# design.net
KiCad netlist of a schematic drawn in Altium Designer
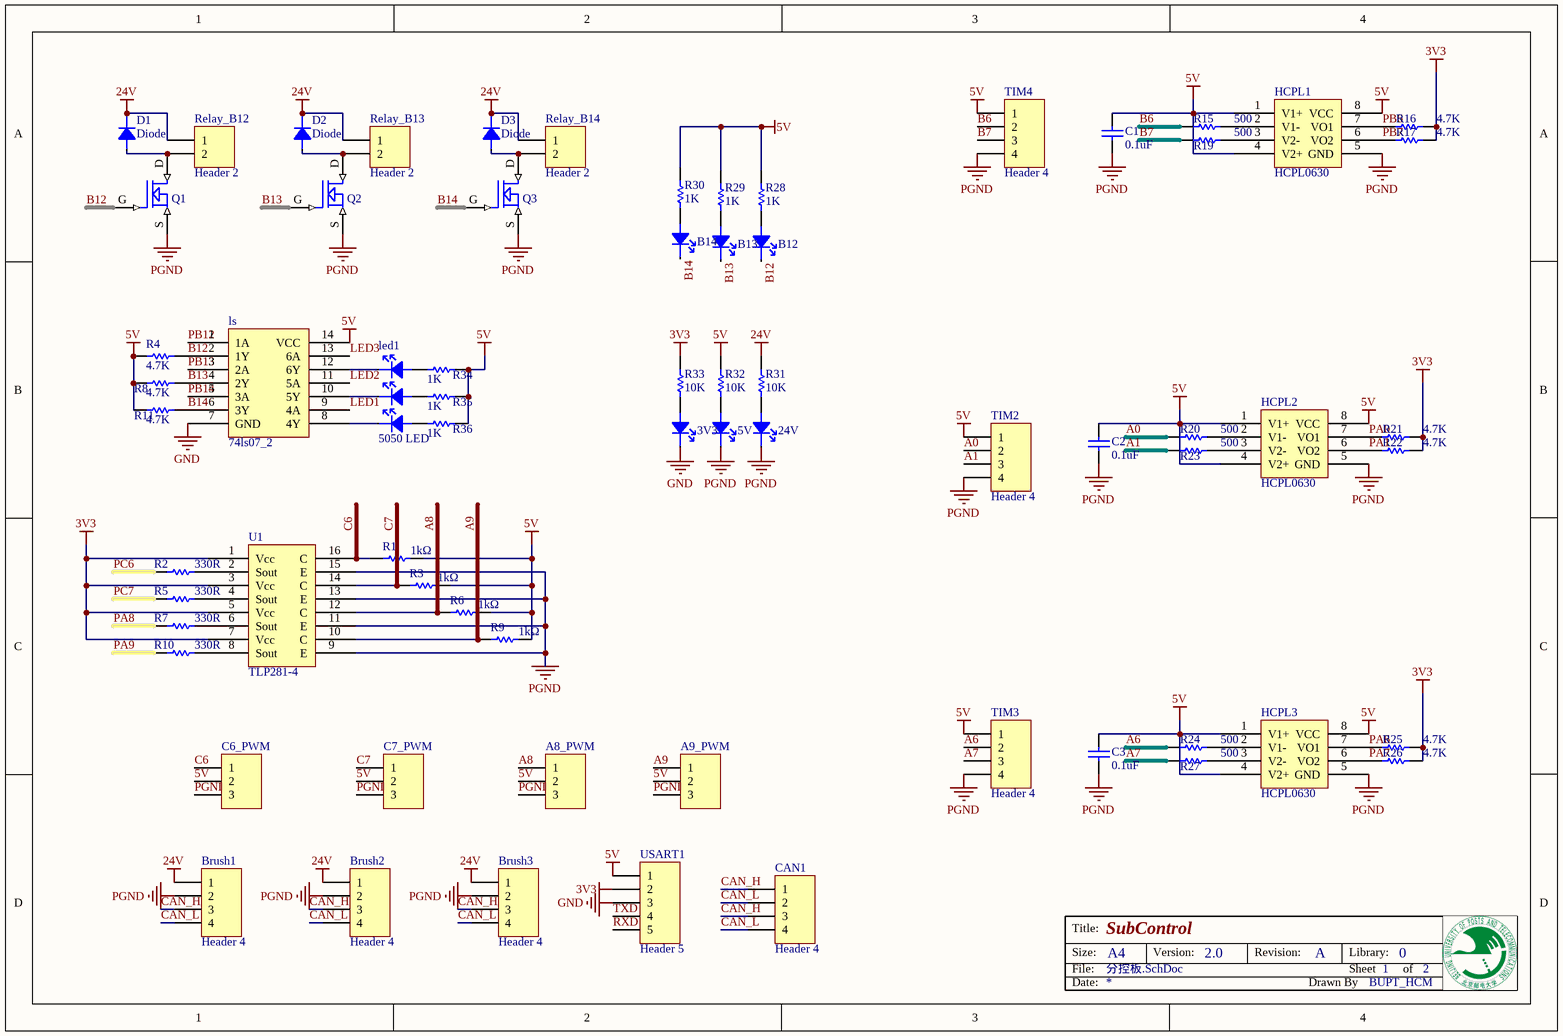
[diagram p0: 分控板.SchDoc]

(export (version "E")
  (design (tool "Eeschema 10.0.6"))
  (components
    (comp (ref "3V3")
      (value "lED")
      (footprint "0805D")
      (description "LED")
      (libsource (lib "K60-mainboard-v3.1") (part "00-D-LED"))
    )
    (comp (ref "5V")
      (value "lED")
      (footprint "0805D")
      (description "LED")
      (libsource (lib "K60-mainboard-v3.1") (part "00-D-LED"))
    )
    (comp (ref "24V")
      (value "lED")
      (footprint "0805D")
      (description "LED")
      (libsource (lib "K60-mainboard-v3.1") (part "00-D-LED"))
    )
    (comp (ref "A8_PWM")
      (value "Header 3")
      (footprint "Green 3P")
      (description "Header, 3-Pin")
      (fields (field (name "PUBLISHER") "Altium Limited"))
      (libsource (lib "Libraries_2014_0618") (part "Header 3"))
    )
    (comp (ref "A9_PWM")
      (value "Header 3")
      (footprint "Green 3P")
      (description "Header, 3-Pin")
      (fields (field (name "PUBLISHER") "Altium Limited"))
      (libsource (lib "Libraries_2014_0618") (part "Header 3"))
    )
    (comp (ref "B12")
      (value "lED")
      (footprint "0805D")
      (description "LED")
      (libsource (lib "K60-mainboard-v3.1") (part "00-D-LED"))
    )
    (comp (ref "B13")
      (value "lED")
      (footprint "0805D")
      (description "LED")
      (libsource (lib "K60-mainboard-v3.1") (part "00-D-LED"))
    )
    (comp (ref "B14")
      (value "lED")
      (footprint "0805D")
      (description "LED")
      (libsource (lib "K60-mainboard-v3.1") (part "00-D-LED"))
    )
    (comp (ref "Brush1")
      (value "Header 4")
      (footprint "Green_4P")
      (description "Header, 4-Pin")
      (fields (field (name "PUBLISHER") "Altium Limited"))
      (libsource (lib "Libraries_2014_0618") (part "Header 4"))
    )
    (comp (ref "Brush2")
      (value "Header 4")
      (footprint "Green_4P")
      (description "Header, 4-Pin")
      (fields (field (name "PUBLISHER") "Altium Limited"))
      (libsource (lib "Libraries_2014_0618") (part "Header 4"))
    )
    (comp (ref "Brush3")
      (value "Header 4")
      (footprint "Green_4P")
      (description "Header, 4-Pin")
      (fields (field (name "PUBLISHER") "Altium Limited"))
      (libsource (lib "Libraries_2014_0618") (part "Header 4"))
    )
    (comp (ref "C1")
      (value "0.1uF")
      (footprint "CAP-MLCC-0603")
      (description "Capacitor")
      (fields (field (name "Comment") "Cap") (field (name "PUBLISHER") "Altium Limited"))
      (libsource (lib "K60-mainboard-v3.1") (part "Cap"))
    )
    (comp (ref "C2")
      (value "0.1uF")
      (footprint "CAP-MLCC-0603")
      (description "Capacitor")
      (fields (field (name "Comment") "Cap") (field (name "PUBLISHER") "Altium Limited"))
      (libsource (lib "K60-mainboard-v3.1") (part "Cap"))
    )
    (comp (ref "C3")
      (value "0.1uF")
      (footprint "CAP-MLCC-0603")
      (description "Capacitor")
      (fields (field (name "Comment") "Cap") (field (name "PUBLISHER") "Altium Limited"))
      (libsource (lib "K60-mainboard-v3.1") (part "Cap"))
    )
    (comp (ref "C6_PWM")
      (value "Header 3")
      (footprint "Green 3P")
      (description "Header, 3-Pin")
      (fields (field (name "PUBLISHER") "Altium Limited"))
      (libsource (lib "Libraries_2014_0618") (part "Header 3"))
    )
    (comp (ref "C7_PWM")
      (value "Header 3")
      (footprint "Green 3P")
      (description "Header, 3-Pin")
      (fields (field (name "PUBLISHER") "Altium Limited"))
      (libsource (lib "Libraries_2014_0618") (part "Header 3"))
    )
    (comp (ref "CAN1")
      (value "Header 4")
      (footprint "Green_4P")
      (description "Header, 4-Pin")
      (fields (field (name "PUBLISHER") "Altium Limited"))
      (libsource (lib "Libraries_2014_0618") (part "Header 4"))
    )
    (comp (ref "D1") (value "Diode") (footprint "SS34") (libsource (lib "K60-mainboard-v3.1") (part "Diode")))
    (comp (ref "D2") (value "Diode") (footprint "SS34") (libsource (lib "K60-mainboard-v3.1") (part "Diode")))
    (comp (ref "D3") (value "Diode") (footprint "SS34") (libsource (lib "K60-mainboard-v3.1") (part "Diode")))
    (comp (ref "HCPL1")
      (value "HCPL0630")
      (footprint "SOIC8")
      (libsource (lib "K60-mainboard-v3.1") (part "HCPL0630"))
    )
    (comp (ref "HCPL2")
      (value "HCPL0630")
      (footprint "SOIC8")
      (libsource (lib "K60-mainboard-v3.1") (part "HCPL0630"))
    )
    (comp (ref "HCPL3")
      (value "HCPL0630")
      (footprint "SOIC8")
      (libsource (lib "K60-mainboard-v3.1") (part "HCPL0630"))
    )
    (comp (ref "led1")
      (value "5050 LED")
      (footprint "5050LED")
      (libsource (lib "K60-mainboard-v3.1") (part "5050 LED"))
    )
    (comp (ref "ls")
      (value "74ls07_2")
      (footprint "74ls07")
      (libsource (lib "K60-mainboard-v3.1") (part "74ls07_2"))
    )
    (comp (ref "Q1")
      (value "MOSFET N")
      (footprint "NMOS_SOT23")
      (libsource (lib "K60-mainboard-v3.1") (part "MOSFET N"))
    )
    (comp (ref "Q2")
      (value "MOSFET N")
      (footprint "NMOS_SOT23")
      (libsource (lib "K60-mainboard-v3.1") (part "MOSFET N"))
    )
    (comp (ref "Q3")
      (value "MOSFET N")
      (footprint "NMOS_SOT23")
      (libsource (lib "K60-mainboard-v3.1") (part "MOSFET N"))
    )
    (comp (ref "R1")
      (value "1kΩ")
      (footprint "RES-0603")
      (description "电阻")
      (fields (field (name "Comment") "RES") (field (name "PUBLISHER") "Altium Limited"))
      (libsource (lib "Libraries_2014_0215") (part "RES"))
    )
    (comp (ref "R2")
      (value "330R")
      (footprint "RES-0603")
      (description "电阻")
      (fields (field (name "Comment") "RES") (field (name "PUBLISHER") "Altium Limited"))
      (libsource (lib "Libraries_2014_0215") (part "RES"))
    )
    (comp (ref "R3")
      (value "1kΩ")
      (footprint "RES-0603")
      (description "电阻")
      (fields (field (name "Comment") "RES") (field (name "PUBLISHER") "Altium Limited"))
      (libsource (lib "Libraries_2014_0215") (part "RES"))
    )
    (comp (ref "R4")
      (value "4.7K")
      (footprint "RES-0603")
      (description "电阻")
      (fields (field (name "Comment") "RES") (field (name "PUBLISHER") "Altium Limited"))
      (libsource (lib "Libraries_2014_0215") (part "RES"))
    )
    (comp (ref "R5")
      (value "330R")
      (footprint "RES-0603")
      (description "电阻")
      (fields (field (name "Comment") "RES") (field (name "PUBLISHER") "Altium Limited"))
      (libsource (lib "Libraries_2014_0215") (part "RES"))
    )
    (comp (ref "R6")
      (value "1kΩ")
      (footprint "RES-0603")
      (description "电阻")
      (fields (field (name "Comment") "RES") (field (name "PUBLISHER") "Altium Limited"))
      (libsource (lib "Libraries_2014_0215") (part "RES"))
    )
    (comp (ref "R7")
      (value "330R")
      (footprint "RES-0603")
      (description "电阻")
      (fields (field (name "Comment") "RES") (field (name "PUBLISHER") "Altium Limited"))
      (libsource (lib "Libraries_2014_0215") (part "RES"))
    )
    (comp (ref "R8")
      (value "4.7K")
      (footprint "RES-0603")
      (description "电阻")
      (fields (field (name "Comment") "RES") (field (name "PUBLISHER") "Altium Limited"))
      (libsource (lib "Libraries_2014_0215") (part "RES"))
    )
    (comp (ref "R9")
      (value "1kΩ")
      (footprint "RES-0603")
      (description "电阻")
      (fields (field (name "Comment") "RES") (field (name "PUBLISHER") "Altium Limited"))
      (libsource (lib "Libraries_2014_0215") (part "RES"))
    )
    (comp (ref "R10")
      (value "330R")
      (footprint "RES-0603")
      (description "电阻")
      (fields (field (name "Comment") "RES") (field (name "PUBLISHER") "Altium Limited"))
      (libsource (lib "Libraries_2014_0215") (part "RES"))
    )
    (comp (ref "R11")
      (value "4.7K")
      (footprint "RES-0603")
      (description "电阻")
      (fields (field (name "Comment") "RES") (field (name "PUBLISHER") "Altium Limited"))
      (libsource (lib "Libraries_2014_0215") (part "RES"))
    )
    (comp (ref "R15")
      (value "500")
      (footprint "RES-0603")
      (description "Resistor")
      (fields (field (name "Comment") "Res1") (field (name "PUBLISHER") "Altium Limited"))
      (libsource (lib "K60-mainboard-v3.1") (part "Res1"))
    )
    (comp (ref "R16")
      (value "4.7K")
      (footprint "RES-0603")
      (description "Resistor")
      (fields (field (name "Comment") "Res1") (field (name "PUBLISHER") "Altium Limited"))
      (libsource (lib "K60-mainboard-v3.1") (part "Res1"))
    )
    (comp (ref "R17")
      (value "4.7K")
      (footprint "RES-0603")
      (description "Resistor")
      (fields (field (name "Comment") "Res1") (field (name "PUBLISHER") "Altium Limited"))
      (libsource (lib "K60-mainboard-v3.1") (part "Res1"))
    )
    (comp (ref "R19")
      (value "500")
      (footprint "RES-0603")
      (description "Resistor")
      (fields (field (name "Comment") "Res1") (field (name "PUBLISHER") "Altium Limited"))
      (libsource (lib "K60-mainboard-v3.1") (part "Res1"))
    )
    (comp (ref "R20")
      (value "500")
      (footprint "RES-0603")
      (description "Resistor")
      (fields (field (name "Comment") "Res1") (field (name "PUBLISHER") "Altium Limited"))
      (libsource (lib "K60-mainboard-v3.1") (part "Res1"))
    )
    (comp (ref "R21")
      (value "4.7K")
      (footprint "RES-0603")
      (description "Resistor")
      (fields (field (name "Comment") "Res1") (field (name "PUBLISHER") "Altium Limited"))
      (libsource (lib "K60-mainboard-v3.1") (part "Res1"))
    )
    (comp (ref "R22")
      (value "4.7K")
      (footprint "RES-0603")
      (description "Resistor")
      (fields (field (name "Comment") "Res1") (field (name "PUBLISHER") "Altium Limited"))
      (libsource (lib "K60-mainboard-v3.1") (part "Res1"))
    )
    (comp (ref "R23")
      (value "500")
      (footprint "RES-0603")
      (description "Resistor")
      (fields (field (name "Comment") "Res1") (field (name "PUBLISHER") "Altium Limited"))
      (libsource (lib "K60-mainboard-v3.1") (part "Res1"))
    )
    (comp (ref "R24")
      (value "500")
      (footprint "RES-0603")
      (description "Resistor")
      (fields (field (name "Comment") "Res1") (field (name "PUBLISHER") "Altium Limited"))
      (libsource (lib "K60-mainboard-v3.1") (part "Res1"))
    )
    (comp (ref "R25")
      (value "4.7K")
      (footprint "RES-0603")
      (description "Resistor")
      (fields (field (name "Comment") "Res1") (field (name "PUBLISHER") "Altium Limited"))
      (libsource (lib "K60-mainboard-v3.1") (part "Res1"))
    )
    (comp (ref "R26")
      (value "4.7K")
      (footprint "RES-0603")
      (description "Resistor")
      (fields (field (name "Comment") "Res1") (field (name "PUBLISHER") "Altium Limited"))
      (libsource (lib "K60-mainboard-v3.1") (part "Res1"))
    )
    (comp (ref "R27")
      (value "500")
      (footprint "RES-0603")
      (description "Resistor")
      (fields (field (name "Comment") "Res1") (field (name "PUBLISHER") "Altium Limited"))
      (libsource (lib "K60-mainboard-v3.1") (part "Res1"))
    )
    (comp (ref "R28")
      (value "1K")
      (footprint "RES-0603")
      (description "电阻")
      (fields (field (name "Comment") "RES") (field (name "PUBLISHER") "Altium Limited"))
      (libsource (lib "Libraries_2014_0215") (part "RES"))
    )
    (comp (ref "R29")
      (value "1K")
      (footprint "RES-0603")
      (description "电阻")
      (fields (field (name "Comment") "RES") (field (name "PUBLISHER") "Altium Limited"))
      (libsource (lib "Libraries_2014_0215") (part "RES"))
    )
    (comp (ref "R30")
      (value "1K")
      (footprint "RES-0603")
      (description "电阻")
      (fields (field (name "Comment") "RES") (field (name "PUBLISHER") "Altium Limited"))
      (libsource (lib "Libraries_2014_0215") (part "RES"))
    )
    (comp (ref "R31")
      (value "10K")
      (footprint "RES-0603")
      (description "电阻")
      (fields (field (name "Comment") "RES") (field (name "PUBLISHER") "Altium Limited"))
      (libsource (lib "Libraries_2014_0215") (part "RES"))
    )
    (comp (ref "R32")
      (value "10K")
      (footprint "RES-0603")
      (description "电阻")
      (fields (field (name "Comment") "RES") (field (name "PUBLISHER") "Altium Limited"))
      (libsource (lib "Libraries_2014_0215") (part "RES"))
    )
    (comp (ref "R33")
      (value "10K")
      (footprint "RES-0603")
      (description "电阻")
      (fields (field (name "Comment") "RES") (field (name "PUBLISHER") "Altium Limited"))
      (libsource (lib "Libraries_2014_0215") (part "RES"))
    )
    (comp (ref "R34")
      (value "1K")
      (footprint "RES-0603")
      (description "电阻")
      (fields (field (name "Comment") "RES") (field (name "PUBLISHER") "Altium Limited"))
      (libsource (lib "Libraries_2014_0215") (part "RES"))
    )
    (comp (ref "R35")
      (value "1K")
      (footprint "RES-0603")
      (description "电阻")
      (fields (field (name "Comment") "RES") (field (name "PUBLISHER") "Altium Limited"))
      (libsource (lib "Libraries_2014_0215") (part "RES"))
    )
    (comp (ref "R36")
      (value "1K")
      (footprint "RES-0603")
      (description "电阻")
      (fields (field (name "Comment") "RES") (field (name "PUBLISHER") "Altium Limited"))
      (libsource (lib "Libraries_2014_0215") (part "RES"))
    )
    (comp (ref "Relay_B12")
      (value "Header 2")
      (footprint "Green_2P")
      (description "Header, 2-Pin")
      (fields (field (name "PUBLISHER") "Altium Limited"))
      (libsource (lib "K60-mainboard-v3.1") (part "Header 2"))
    )
    (comp (ref "Relay_B13")
      (value "Header 2")
      (footprint "Green_2P")
      (description "Header, 2-Pin")
      (fields (field (name "PUBLISHER") "Altium Limited"))
      (libsource (lib "K60-mainboard-v3.1") (part "Header 2"))
    )
    (comp (ref "Relay_B14")
      (value "Header 2")
      (footprint "Green_2P")
      (description "Header, 2-Pin")
      (fields (field (name "PUBLISHER") "Altium Limited"))
      (libsource (lib "K60-mainboard-v3.1") (part "Header 2"))
    )
    (comp (ref "TIM2")
      (value "Header 4")
      (footprint "Green_4P")
      (description "Header, 4-Pin")
      (fields (field (name "PUBLISHER") "Altium Limited"))
      (libsource (lib "Libraries_2014_0618") (part "Header 4"))
    )
    (comp (ref "TIM3")
      (value "Header 4")
      (footprint "Green_4P")
      (description "Header, 4-Pin")
      (fields (field (name "PUBLISHER") "Altium Limited"))
      (libsource (lib "Libraries_2014_0618") (part "Header 4"))
    )
    (comp (ref "TIM4")
      (value "Header 4")
      (footprint "Green_4P")
      (description "Header, 4-Pin")
      (fields (field (name "PUBLISHER") "Altium Limited"))
      (libsource (lib "Libraries_2014_0618") (part "Header 4"))
    )
    (comp (ref "U1")
      (value "TLP281-4")
      (footprint "SOP16")
      (description "TLP521-4,TLP281-4")
      (libsource (lib "Libraries_2014_0215") (part "IC-TLP521-4"))
    )
    (comp (ref "USART1")
      (value "Header 5")
      (footprint "Green_5P")
      (description "Header, 5-Pin")
      (fields (field (name "PUBLISHER") "Altium Limited"))
      (libsource (lib "Libraries_2014_0618") (part "Header 5"))
    )
  )
  (nets
    (net (code "1") (name "/A0") (class "Default")
      (node (ref "R20") (pin "1") (pinfunction "1_1") (pintype "passive"))
      (node (ref "TIM2") (pin "2") (pinfunction "2_2") (pintype "passive"))
    )
    (net (code "2") (name "/A1") (class "Default")
      (node (ref "R23") (pin "1") (pinfunction "1_1") (pintype "passive"))
      (node (ref "TIM2") (pin "3") (pinfunction "3_3") (pintype "passive"))
    )
    (net (code "3") (name "/A6") (class "Default")
      (node (ref "R24") (pin "1") (pinfunction "1_1") (pintype "passive"))
      (node (ref "TIM3") (pin "2") (pinfunction "2_2") (pintype "passive"))
    )
    (net (code "4") (name "/A7") (class "Default")
      (node (ref "R27") (pin "1") (pinfunction "1_1") (pintype "passive"))
      (node (ref "TIM3") (pin "3") (pinfunction "3_3") (pintype "passive"))
    )
    (net (code "5") (name "/A8") (class "Default")
      (node (ref "A8_PWM") (pin "1") (pinfunction "1_1") (pintype "passive"))
      (node (ref "R6") (pin "1") (pinfunction "1_1") (pintype "passive"))
      (node (ref "U1") (pin "12") (pinfunction "C_12") (pintype "power_in"))
    )
    (net (code "6") (name "/A9") (class "Default")
      (node (ref "A9_PWM") (pin "1") (pinfunction "1_1") (pintype "passive"))
      (node (ref "R9") (pin "1") (pinfunction "1_1") (pintype "passive"))
      (node (ref "U1") (pin "10") (pinfunction "C_10") (pintype "power_in"))
    )
    (net (code "7") (name "/B6") (class "Default")
      (node (ref "R15") (pin "1") (pinfunction "1_1") (pintype "passive"))
      (node (ref "TIM4") (pin "2") (pinfunction "2_2") (pintype "passive"))
    )
    (net (code "8") (name "/B7") (class "Default")
      (node (ref "R19") (pin "1") (pinfunction "1_1") (pintype "passive"))
      (node (ref "TIM4") (pin "3") (pinfunction "3_3") (pintype "passive"))
    )
    (net (code "9") (name "/B12") (class "Default")
      (node (ref "B12") (pin "K") (pinfunction "2_K") (pintype "passive"))
      (node (ref "Q1") (pin "G") (pinfunction "G_G") (pintype "input"))
      (node (ref "R4") (pin "2") (pinfunction "2_2") (pintype "passive"))
      (node (ref "ls") (pin "2") (pinfunction "1Y_2") (pintype "passive"))
    )
    (net (code "10") (name "/B13") (class "Default")
      (node (ref "B13") (pin "K") (pinfunction "2_K") (pintype "passive"))
      (node (ref "Q2") (pin "G") (pinfunction "G_G") (pintype "input"))
      (node (ref "R8") (pin "2") (pinfunction "2_2") (pintype "passive"))
      (node (ref "ls") (pin "4") (pinfunction "2Y_4") (pintype "passive"))
    )
    (net (code "11") (name "/B14") (class "Default")
      (node (ref "B14") (pin "K") (pinfunction "2_K") (pintype "passive"))
      (node (ref "Q3") (pin "G") (pinfunction "G_G") (pintype "input"))
      (node (ref "R11") (pin "2") (pinfunction "2_2") (pintype "passive"))
      (node (ref "ls") (pin "6") (pinfunction "3Y_6") (pintype "passive"))
    )
    (net (code "12") (name "/C6") (class "Default")
      (node (ref "C6_PWM") (pin "1") (pinfunction "1_1") (pintype "passive"))
      (node (ref "R1") (pin "1") (pinfunction "1_1") (pintype "passive"))
      (node (ref "U1") (pin "16") (pinfunction "C_16") (pintype "power_in"))
    )
    (net (code "13") (name "/C7") (class "Default")
      (node (ref "C7_PWM") (pin "1") (pinfunction "1_1") (pintype "passive"))
      (node (ref "R3") (pin "1") (pinfunction "1_1") (pintype "passive"))
      (node (ref "U1") (pin "14") (pinfunction "C_14") (pintype "power_in"))
    )
    (net (code "14") (name "/CAN_H") (class "Default")
      (node (ref "Brush1") (pin "3") (pinfunction "3_3") (pintype "passive"))
      (node (ref "Brush2") (pin "3") (pinfunction "3_3") (pintype "passive"))
      (node (ref "Brush3") (pin "3") (pinfunction "3_3") (pintype "passive"))
      (node (ref "CAN1") (pin "1") (pinfunction "1_1") (pintype "passive"))
      (node (ref "CAN1") (pin "3") (pinfunction "3_3") (pintype "passive"))
    )
    (net (code "15") (name "/CAN_L") (class "Default")
      (node (ref "Brush1") (pin "4") (pinfunction "4_4") (pintype "passive"))
      (node (ref "Brush2") (pin "4") (pinfunction "4_4") (pintype "passive"))
      (node (ref "Brush3") (pin "4") (pinfunction "4_4") (pintype "passive"))
      (node (ref "CAN1") (pin "2") (pinfunction "2_2") (pintype "passive"))
      (node (ref "CAN1") (pin "4") (pinfunction "4_4") (pintype "passive"))
    )
    (net (code "16") (name "/LED1") (class "Default")
      (node (ref "ls") (pin "9") (pinfunction "4A_9") (pintype "passive"))
    )
    (net (code "17") (name "/LED2") (class "Default")
      (node (ref "ls") (pin "11") (pinfunction "5A_11") (pintype "passive"))
    )
    (net (code "18") (name "/LED3") (class "Default")
      (node (ref "ls") (pin "13") (pinfunction "6A_13") (pintype "passive"))
    )
    (net (code "19") (name "/PA0") (class "Default")
      (node (ref "HCPL2") (pin "7") (pinfunction "VO1_7") (pintype "passive"))
      (node (ref "R21") (pin "1") (pinfunction "1_1") (pintype "passive"))
    )
    (net (code "20") (name "/PA1") (class "Default")
      (node (ref "HCPL2") (pin "6") (pinfunction "VO2_6") (pintype "passive"))
      (node (ref "R22") (pin "1") (pinfunction "1_1") (pintype "passive"))
    )
    (net (code "21") (name "/PA6") (class "Default")
      (node (ref "HCPL3") (pin "7") (pinfunction "VO1_7") (pintype "passive"))
      (node (ref "R25") (pin "1") (pinfunction "1_1") (pintype "passive"))
    )
    (net (code "22") (name "/PA7") (class "Default")
      (node (ref "HCPL3") (pin "6") (pinfunction "VO2_6") (pintype "passive"))
      (node (ref "R26") (pin "1") (pinfunction "1_1") (pintype "passive"))
    )
    (net (code "23") (name "/PA8") (class "Default")
      (node (ref "R7") (pin "1") (pinfunction "1_1") (pintype "passive"))
    )
    (net (code "24") (name "/PA9") (class "Default")
      (node (ref "R10") (pin "1") (pinfunction "1_1") (pintype "passive"))
    )
    (net (code "25") (name "/PB6") (class "Default")
      (node (ref "HCPL1") (pin "7") (pinfunction "VO1_7") (pintype "passive"))
      (node (ref "R16") (pin "1") (pinfunction "1_1") (pintype "passive"))
    )
    (net (code "26") (name "/PB7") (class "Default")
      (node (ref "HCPL1") (pin "6") (pinfunction "VO2_6") (pintype "passive"))
      (node (ref "R17") (pin "1") (pinfunction "1_1") (pintype "passive"))
    )
    (net (code "27") (name "/PB12") (class "Default")
      (node (ref "ls") (pin "1") (pinfunction "1A_1") (pintype "passive"))
    )
    (net (code "28") (name "/PB13") (class "Default")
      (node (ref "ls") (pin "3") (pinfunction "2A_3") (pintype "passive"))
    )
    (net (code "29") (name "/PB14") (class "Default")
      (node (ref "ls") (pin "5") (pinfunction "3A_5") (pintype "passive"))
    )
    (net (code "30") (name "/PC6") (class "Default")
      (node (ref "R2") (pin "1") (pinfunction "1_1") (pintype "passive"))
    )
    (net (code "31") (name "/PC7") (class "Default")
      (node (ref "R5") (pin "1") (pinfunction "1_1") (pintype "passive"))
    )
    (net (code "32") (name "/RXD") (class "Default")
      (node (ref "USART1") (pin "5") (pinfunction "5_5") (pintype "passive"))
    )
    (net (code "33") (name "/TXD") (class "Default")
      (node (ref "USART1") (pin "4") (pinfunction "4_4") (pintype "passive"))
    )
    (net (code "34") (name "3V3") (class "Default")
      (node (ref "R16") (pin "2") (pinfunction "2_2") (pintype "passive"))
      (node (ref "R17") (pin "2") (pinfunction "2_2") (pintype "passive"))
      (node (ref "R21") (pin "2") (pinfunction "2_2") (pintype "passive"))
      (node (ref "R22") (pin "2") (pinfunction "2_2") (pintype "passive"))
      (node (ref "R25") (pin "2") (pinfunction "2_2") (pintype "passive"))
      (node (ref "R26") (pin "2") (pinfunction "2_2") (pintype "passive"))
      (node (ref "R33") (pin "1") (pinfunction "1_1") (pintype "passive"))
      (node (ref "U1") (pin "1") (pinfunction "Vcc_1") (pintype "power_in"))
      (node (ref "U1") (pin "3") (pinfunction "Vcc_3") (pintype "power_in"))
      (node (ref "U1") (pin "5") (pinfunction "Vcc_5") (pintype "power_in"))
      (node (ref "U1") (pin "7") (pinfunction "Vcc_7") (pintype "power_in"))
      (node (ref "USART1") (pin "2") (pinfunction "2_2") (pintype "passive"))
    )
    (net (code "35") (name "5V") (class "Default")
      (node (ref "A8_PWM") (pin "2") (pinfunction "2_2") (pintype "passive"))
      (node (ref "A9_PWM") (pin "2") (pinfunction "2_2") (pintype "passive"))
      (node (ref "C1") (pin "1") (pinfunction "1_1") (pintype "passive"))
      (node (ref "C2") (pin "1") (pinfunction "1_1") (pintype "passive"))
      (node (ref "C3") (pin "1") (pinfunction "1_1") (pintype "passive"))
      (node (ref "C6_PWM") (pin "2") (pinfunction "2_2") (pintype "passive"))
      (node (ref "C7_PWM") (pin "2") (pinfunction "2_2") (pintype "passive"))
      (node (ref "HCPL1") (pin "1") (pinfunction "V1+_1") (pintype "passive"))
      (node (ref "HCPL1") (pin "4") (pinfunction "V2+_4") (pintype "passive"))
      (node (ref "HCPL1") (pin "8") (pinfunction "VCC_8") (pintype "passive"))
      (node (ref "HCPL2") (pin "1") (pinfunction "V1+_1") (pintype "passive"))
      (node (ref "HCPL2") (pin "4") (pinfunction "V2+_4") (pintype "passive"))
      (node (ref "HCPL2") (pin "8") (pinfunction "VCC_8") (pintype "passive"))
      (node (ref "HCPL3") (pin "1") (pinfunction "V1+_1") (pintype "passive"))
      (node (ref "HCPL3") (pin "4") (pinfunction "V2+_4") (pintype "passive"))
      (node (ref "HCPL3") (pin "8") (pinfunction "VCC_8") (pintype "passive"))
      (node (ref "R1") (pin "2") (pinfunction "2_2") (pintype "passive"))
      (node (ref "R11") (pin "1") (pinfunction "1_1") (pintype "passive"))
      (node (ref "R28") (pin "1") (pinfunction "1_1") (pintype "passive"))
      (node (ref "R29") (pin "1") (pinfunction "1_1") (pintype "passive"))
      (node (ref "R3") (pin "2") (pinfunction "2_2") (pintype "passive"))
      (node (ref "R30") (pin "1") (pinfunction "1_1") (pintype "passive"))
      (node (ref "R32") (pin "1") (pinfunction "1_1") (pintype "passive"))
      (node (ref "R34") (pin "2") (pinfunction "2_2") (pintype "passive"))
      (node (ref "R35") (pin "2") (pinfunction "2_2") (pintype "passive"))
      (node (ref "R36") (pin "2") (pinfunction "2_2") (pintype "passive"))
      (node (ref "R4") (pin "1") (pinfunction "1_1") (pintype "passive"))
      (node (ref "R6") (pin "2") (pinfunction "2_2") (pintype "passive"))
      (node (ref "R8") (pin "1") (pinfunction "1_1") (pintype "passive"))
      (node (ref "R9") (pin "2") (pinfunction "2_2") (pintype "passive"))
      (node (ref "TIM2") (pin "1") (pinfunction "1_1") (pintype "passive"))
      (node (ref "TIM3") (pin "1") (pinfunction "1_1") (pintype "passive"))
      (node (ref "TIM4") (pin "1") (pinfunction "1_1") (pintype "passive"))
      (node (ref "USART1") (pin "1") (pinfunction "1_1") (pintype "passive"))
      (node (ref "ls") (pin "14") (pinfunction "VCC_14") (pintype "passive"))
    )
    (net (code "36") (name "24V") (class "Default")
      (node (ref "Brush1") (pin "1") (pinfunction "1_1") (pintype "passive"))
      (node (ref "Brush2") (pin "1") (pinfunction "1_1") (pintype "passive"))
      (node (ref "Brush3") (pin "1") (pinfunction "1_1") (pintype "passive"))
      (node (ref "D1") (pin "K") (pinfunction "2_K") (pintype "passive"))
      (node (ref "D2") (pin "K") (pinfunction "2_K") (pintype "passive"))
      (node (ref "D3") (pin "K") (pinfunction "2_K") (pintype "passive"))
      (node (ref "R31") (pin "1") (pinfunction "1_1") (pintype "passive"))
      (node (ref "Relay_B12") (pin "1") (pinfunction "1_1") (pintype "passive"))
      (node (ref "Relay_B13") (pin "1") (pinfunction "1_1") (pintype "passive"))
      (node (ref "Relay_B14") (pin "1") (pinfunction "1_1") (pintype "passive"))
    )
    (net (code "37") (name "GND") (class "Default")
      (node (ref "3V3") (pin "K") (pinfunction "2_K") (pintype "passive"))
      (node (ref "USART1") (pin "3") (pinfunction "3_3") (pintype "passive"))
      (node (ref "ls") (pin "7") (pinfunction "GND_7") (pintype "passive"))
    )
    (net (code "38") (name "Net-(3V3-1)") (class "Default")
      (node (ref "3V3") (pin "A") (pinfunction "1_A") (pintype "passive"))
      (node (ref "R33") (pin "2") (pinfunction "2_2") (pintype "passive"))
    )
    (net (code "39") (name "Net-(5V-1)") (class "Default")
      (node (ref "5V") (pin "A") (pinfunction "1_A") (pintype "passive"))
      (node (ref "R32") (pin "2") (pinfunction "2_2") (pintype "passive"))
    )
    (net (code "40") (name "Net-(24V-1)") (class "Default")
      (node (ref "24V") (pin "A") (pinfunction "1_A") (pintype "passive"))
      (node (ref "R31") (pin "2") (pinfunction "2_2") (pintype "passive"))
    )
    (net (code "41") (name "Net-(B12-1)") (class "Default")
      (node (ref "B12") (pin "A") (pinfunction "1_A") (pintype "passive"))
      (node (ref "R28") (pin "2") (pinfunction "2_2") (pintype "passive"))
    )
    (net (code "42") (name "Net-(B13-1)") (class "Default")
      (node (ref "B13") (pin "A") (pinfunction "1_A") (pintype "passive"))
      (node (ref "R29") (pin "2") (pinfunction "2_2") (pintype "passive"))
    )
    (net (code "43") (name "Net-(B14-1)") (class "Default")
      (node (ref "B14") (pin "A") (pinfunction "1_A") (pintype "passive"))
      (node (ref "R30") (pin "2") (pinfunction "2_2") (pintype "passive"))
    )
    (net (code "44") (name "Net-(D1-1)") (class "Default")
      (node (ref "D1") (pin "A") (pinfunction "1_A") (pintype "passive"))
      (node (ref "Q1") (pin "D") (pinfunction "D_D") (pintype "input"))
      (node (ref "Relay_B12") (pin "2") (pinfunction "2_2") (pintype "passive"))
    )
    (net (code "45") (name "Net-(D2-1)") (class "Default")
      (node (ref "D2") (pin "A") (pinfunction "1_A") (pintype "passive"))
      (node (ref "Q2") (pin "D") (pinfunction "D_D") (pintype "input"))
      (node (ref "Relay_B13") (pin "2") (pinfunction "2_2") (pintype "passive"))
    )
    (net (code "46") (name "Net-(D3-1)") (class "Default")
      (node (ref "D3") (pin "A") (pinfunction "1_A") (pintype "passive"))
      (node (ref "Q3") (pin "D") (pinfunction "D_D") (pintype "input"))
      (node (ref "Relay_B14") (pin "2") (pinfunction "2_2") (pintype "passive"))
    )
    (net (code "47") (name "Net-(HCPL1-V1-)") (class "Default")
      (node (ref "HCPL1") (pin "2") (pinfunction "V1-_2") (pintype "passive"))
      (node (ref "R15") (pin "2") (pinfunction "2_2") (pintype "passive"))
    )
    (net (code "48") (name "Net-(HCPL1-V2-)") (class "Default")
      (node (ref "HCPL1") (pin "3") (pinfunction "V2-_3") (pintype "passive"))
      (node (ref "R19") (pin "2") (pinfunction "2_2") (pintype "passive"))
    )
    (net (code "49") (name "Net-(HCPL2-V1-)") (class "Default")
      (node (ref "HCPL2") (pin "2") (pinfunction "V1-_2") (pintype "passive"))
      (node (ref "R20") (pin "2") (pinfunction "2_2") (pintype "passive"))
    )
    (net (code "50") (name "Net-(HCPL2-V2-)") (class "Default")
      (node (ref "HCPL2") (pin "3") (pinfunction "V2-_3") (pintype "passive"))
      (node (ref "R23") (pin "2") (pinfunction "2_2") (pintype "passive"))
    )
    (net (code "51") (name "Net-(HCPL3-V1-)") (class "Default")
      (node (ref "HCPL3") (pin "2") (pinfunction "V1-_2") (pintype "passive"))
      (node (ref "R24") (pin "2") (pinfunction "2_2") (pintype "passive"))
    )
    (net (code "52") (name "Net-(HCPL3-V2-)") (class "Default")
      (node (ref "HCPL3") (pin "3") (pinfunction "V2-_3") (pintype "passive"))
      (node (ref "R27") (pin "2") (pinfunction "2_2") (pintype "passive"))
    )
    (net (code "53") (name "Net-(R2-Pad2)") (class "Default")
      (node (ref "R2") (pin "2") (pinfunction "2_2") (pintype "passive"))
      (node (ref "U1") (pin "2") (pinfunction "Sout_2") (pintype "power_in"))
    )
    (net (code "54") (name "Net-(R5-Pad2)") (class "Default")
      (node (ref "R5") (pin "2") (pinfunction "2_2") (pintype "passive"))
      (node (ref "U1") (pin "4") (pinfunction "Sout_4") (pintype "power_in"))
    )
    (net (code "55") (name "Net-(R7-Pad2)") (class "Default")
      (node (ref "R7") (pin "2") (pinfunction "2_2") (pintype "passive"))
      (node (ref "U1") (pin "6") (pinfunction "Sout_6") (pintype "power_in"))
    )
    (net (code "56") (name "Net-(R10-Pad2)") (class "Default")
      (node (ref "R10") (pin "2") (pinfunction "2_2") (pintype "passive"))
      (node (ref "U1") (pin "8") (pinfunction "Sout_8") (pintype "power_in"))
    )
    (net (code "57") (name "Net-(led1-1)") (class "Default")
      (node (ref "R34") (pin "1") (pinfunction "1_1") (pintype "passive"))
      (node (ref "led1") (pin "A1") (pinfunction "1_A1") (pintype "passive"))
    )
    (net (code "58") (name "Net-(led1-2)") (class "Default")
      (node (ref "led1") (pin "K1") (pinfunction "2_K1") (pintype "passive"))
      (node (ref "ls") (pin "12") (pinfunction "6Y_12") (pintype "passive"))
    )
    (net (code "59") (name "Net-(led1-3)") (class "Default")
      (node (ref "R35") (pin "1") (pinfunction "1_1") (pintype "passive"))
      (node (ref "led1") (pin "A2") (pinfunction "3_A2") (pintype "passive"))
    )
    (net (code "60") (name "Net-(led1-4)") (class "Default")
      (node (ref "led1") (pin "K2") (pinfunction "4_K2") (pintype "passive"))
      (node (ref "ls") (pin "10") (pinfunction "5Y_10") (pintype "passive"))
    )
    (net (code "61") (name "Net-(led1-5)") (class "Default")
      (node (ref "R36") (pin "1") (pinfunction "1_1") (pintype "passive"))
      (node (ref "led1") (pin "A3") (pinfunction "5_A3") (pintype "passive"))
    )
    (net (code "62") (name "Net-(led1-6)") (class "Default")
      (node (ref "led1") (pin "K3") (pinfunction "6_K3") (pintype "passive"))
      (node (ref "ls") (pin "8") (pinfunction "4Y_8") (pintype "passive"))
    )
    (net (code "63") (name "PGND") (class "Default")
      (node (ref "24V") (pin "K") (pinfunction "2_K") (pintype "passive"))
      (node (ref "5V") (pin "K") (pinfunction "2_K") (pintype "passive"))
      (node (ref "A8_PWM") (pin "3") (pinfunction "3_3") (pintype "passive"))
      (node (ref "A9_PWM") (pin "3") (pinfunction "3_3") (pintype "passive"))
      (node (ref "Brush1") (pin "2") (pinfunction "2_2") (pintype "passive"))
      (node (ref "Brush2") (pin "2") (pinfunction "2_2") (pintype "passive"))
      (node (ref "Brush3") (pin "2") (pinfunction "2_2") (pintype "passive"))
      (node (ref "C1") (pin "2") (pinfunction "2_2") (pintype "passive"))
      (node (ref "C2") (pin "2") (pinfunction "2_2") (pintype "passive"))
      (node (ref "C3") (pin "2") (pinfunction "2_2") (pintype "passive"))
      (node (ref "C6_PWM") (pin "3") (pinfunction "3_3") (pintype "passive"))
      (node (ref "C7_PWM") (pin "3") (pinfunction "3_3") (pintype "passive"))
      (node (ref "HCPL1") (pin "5") (pinfunction "GND_5") (pintype "passive"))
      (node (ref "HCPL2") (pin "5") (pinfunction "GND_5") (pintype "passive"))
      (node (ref "HCPL3") (pin "5") (pinfunction "GND_5") (pintype "passive"))
      (node (ref "Q1") (pin "S") (pinfunction "S_S") (pintype "input"))
      (node (ref "Q2") (pin "S") (pinfunction "S_S") (pintype "input"))
      (node (ref "Q3") (pin "S") (pinfunction "S_S") (pintype "input"))
      (node (ref "TIM2") (pin "4") (pinfunction "4_4") (pintype "passive"))
      (node (ref "TIM3") (pin "4") (pinfunction "4_4") (pintype "passive"))
      (node (ref "TIM4") (pin "4") (pinfunction "4_4") (pintype "passive"))
      (node (ref "U1") (pin "11") (pinfunction "E_11") (pintype "power_in"))
      (node (ref "U1") (pin "13") (pinfunction "E_13") (pintype "power_in"))
      (node (ref "U1") (pin "15") (pinfunction "E_15") (pintype "power_in"))
      (node (ref "U1") (pin "9") (pinfunction "E_9") (pintype "power_in"))
    )
  )
)
